# Analog_Inputs.net
KiCad netlist of a schematic drawn in Altium Designer
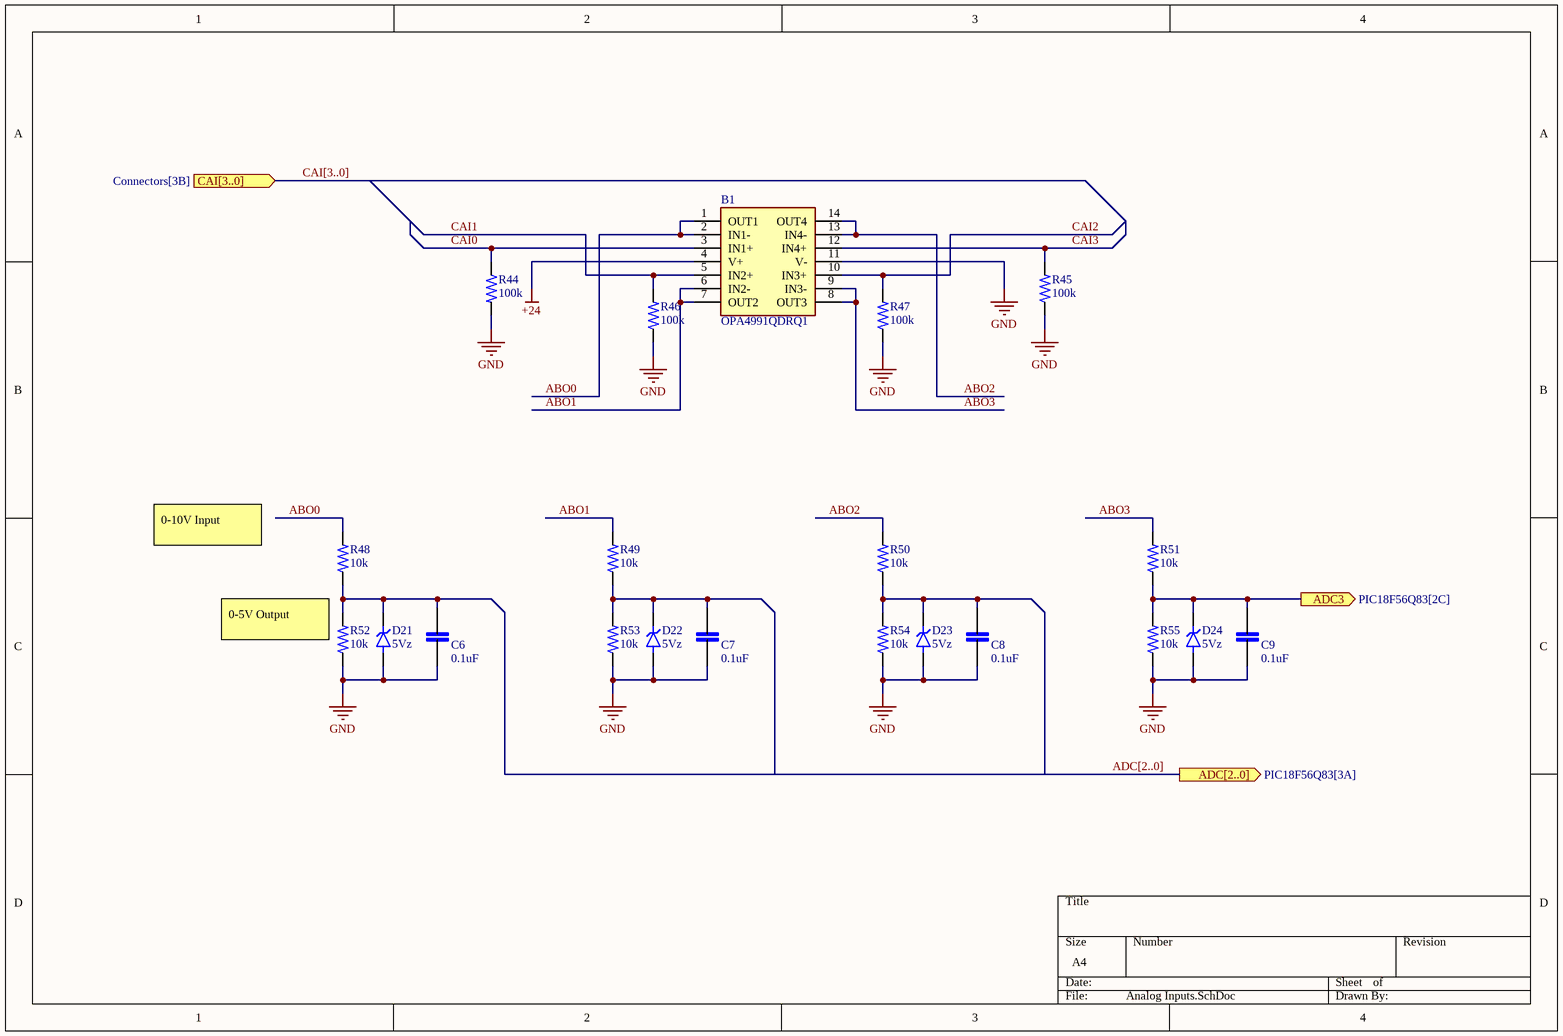
[diagram p0: Analog Inputs.SchDoc]

(export (version "E")
  (design (tool "Eeschema 10.0.6"))
  (components
    (comp (ref "B1")
      (value "OPA4991QDRQ1")
      (footprint "OPA4991QDRQ1")
      (fields (field (name "MOUSER PART NUMBER") "595-OPA4991QDRQ1"))
      (libsource (lib "OP AMP") (part "OPA4991QDRQ1"))
    )
    (comp (ref "C6")
      (value "0.1uF")
      (footprint "0805")
      (fields (field (name "MP") "LD051A121KAB2A") (field (name "MF") "AVX"))
      (libsource (lib "Capacitors SMD") (part "0805_Capacitor"))
    )
    (comp (ref "C7")
      (value "0.1uF")
      (footprint "0805")
      (fields (field (name "MP") "LD051A121KAB2A") (field (name "MF") "AVX"))
      (libsource (lib "Capacitors SMD") (part "0805_Capacitor"))
    )
    (comp (ref "C8")
      (value "0.1uF")
      (footprint "0805")
      (fields (field (name "MP") "LD051A121KAB2A") (field (name "MF") "AVX"))
      (libsource (lib "Capacitors SMD") (part "0805_Capacitor"))
    )
    (comp (ref "C9")
      (value "0.1uF")
      (footprint "0805")
      (fields (field (name "MP") "LD051A121KAB2A") (field (name "MF") "AVX"))
      (libsource (lib "Capacitors SMD") (part "0805_Capacitor"))
    )
    (comp (ref "D21")
      (value "5Vz")
      (footprint "SOD123")
      (fields (field (name "MP") "1SMA5926") (field (name "MF") "Taiwan Semiconductor"))
      (libsource (lib "Diodes SMD") (part "SOD123 - Zener Diode"))
    )
    (comp (ref "D22")
      (value "5Vz")
      (footprint "SOD123")
      (fields (field (name "MP") "1SMA5926") (field (name "MF") "Taiwan Semiconductor"))
      (libsource (lib "Diodes SMD") (part "SOD123 - Zener Diode"))
    )
    (comp (ref "D23")
      (value "5Vz")
      (footprint "SOD123")
      (fields (field (name "MP") "1SMA5926") (field (name "MF") "Taiwan Semiconductor"))
      (libsource (lib "Diodes SMD") (part "SOD123 - Zener Diode"))
    )
    (comp (ref "D24")
      (value "5Vz")
      (footprint "SOD123")
      (fields (field (name "MP") "1SMA5926") (field (name "MF") "Taiwan Semiconductor"))
      (libsource (lib "Diodes SMD") (part "SOD123 - Zener Diode"))
    )
    (comp (ref "R44")
      (value "100k")
      (footprint "0805")
      (fields
        (field (name "MP") "2-2176053-0")
        (field (name "TOLERANCE") "1%")
        (field (name "MF") "TE Connectivity")
      )
      (libsource (lib "Resistors SMD") (part "0805_Resistor"))
    )
    (comp (ref "R45")
      (value "100k")
      (footprint "0805")
      (fields
        (field (name "MP") "2-2176053-0")
        (field (name "TOLERANCE") "1%")
        (field (name "MF") "TE Connectivity")
      )
      (libsource (lib "Resistors SMD") (part "0805_Resistor"))
    )
    (comp (ref "R46")
      (value "100k")
      (footprint "0805")
      (fields
        (field (name "MP") "2-2176053-0")
        (field (name "TOLERANCE") "1%")
        (field (name "MF") "TE Connectivity")
      )
      (libsource (lib "Resistors SMD") (part "0805_Resistor"))
    )
    (comp (ref "R47")
      (value "100k")
      (footprint "0805")
      (fields
        (field (name "MP") "2-2176053-0")
        (field (name "TOLERANCE") "1%")
        (field (name "MF") "TE Connectivity")
      )
      (libsource (lib "Resistors SMD") (part "0805_Resistor"))
    )
    (comp (ref "R48")
      (value "10k")
      (footprint "0805")
      (fields
        (field (name "MP") "2-2176053-0")
        (field (name "TOLERANCE") "1%")
        (field (name "MF") "TE Connectivity")
      )
      (libsource (lib "Resistors SMD") (part "0805_Resistor"))
    )
    (comp (ref "R49")
      (value "10k")
      (footprint "0805")
      (fields
        (field (name "MP") "2-2176053-0")
        (field (name "TOLERANCE") "1%")
        (field (name "MF") "TE Connectivity")
      )
      (libsource (lib "Resistors SMD") (part "0805_Resistor"))
    )
    (comp (ref "R50")
      (value "10k")
      (footprint "0805")
      (fields
        (field (name "MP") "2-2176053-0")
        (field (name "TOLERANCE") "1%")
        (field (name "MF") "TE Connectivity")
      )
      (libsource (lib "Resistors SMD") (part "0805_Resistor"))
    )
    (comp (ref "R51")
      (value "10k")
      (footprint "0805")
      (fields
        (field (name "MP") "2-2176053-0")
        (field (name "TOLERANCE") "1%")
        (field (name "MF") "TE Connectivity")
      )
      (libsource (lib "Resistors SMD") (part "0805_Resistor"))
    )
    (comp (ref "R52")
      (value "10k")
      (footprint "0805")
      (fields
        (field (name "MP") "2-2176053-0")
        (field (name "TOLERANCE") "1%")
        (field (name "MF") "TE Connectivity")
      )
      (libsource (lib "Resistors SMD") (part "0805_Resistor"))
    )
    (comp (ref "R53")
      (value "10k")
      (footprint "0805")
      (fields
        (field (name "MP") "2-2176053-0")
        (field (name "TOLERANCE") "1%")
        (field (name "MF") "TE Connectivity")
      )
      (libsource (lib "Resistors SMD") (part "0805_Resistor"))
    )
    (comp (ref "R54")
      (value "10k")
      (footprint "0805")
      (fields
        (field (name "MP") "2-2176053-0")
        (field (name "TOLERANCE") "1%")
        (field (name "MF") "TE Connectivity")
      )
      (libsource (lib "Resistors SMD") (part "0805_Resistor"))
    )
    (comp (ref "R55")
      (value "10k")
      (footprint "0805")
      (fields
        (field (name "MP") "2-2176053-0")
        (field (name "TOLERANCE") "1%")
        (field (name "MF") "TE Connectivity")
      )
      (libsource (lib "Resistors SMD") (part "0805_Resistor"))
    )
  )
  (nets
    (net (code "4") (name "+24") (class "Default")
      (node (ref "B1") (pin "4") (pinfunction "V+_4") (pintype "passive"))
    )
    (net (code "5") (name "/ABO0") (class "Default")
      (node (ref "B1") (pin "1") (pinfunction "OUT1_1") (pintype "passive"))
      (node (ref "B1") (pin "2") (pinfunction "IN1-_2") (pintype "passive"))
      (node (ref "R48") (pin "2") (pinfunction "2_2") (pintype "passive"))
    )
    (net (code "6") (name "/ABO1") (class "Default")
      (node (ref "B1") (pin "6") (pinfunction "IN2-_6") (pintype "passive"))
      (node (ref "B1") (pin "7") (pinfunction "OUT2_7") (pintype "passive"))
      (node (ref "R49") (pin "2") (pinfunction "2_2") (pintype "passive"))
    )
    (net (code "7") (name "/ABO2") (class "Default")
      (node (ref "B1") (pin "13") (pinfunction "IN4-_13") (pintype "passive"))
      (node (ref "B1") (pin "14") (pinfunction "OUT4_14") (pintype "passive"))
      (node (ref "R50") (pin "2") (pinfunction "2_2") (pintype "passive"))
    )
    (net (code "8") (name "/ABO3") (class "Default")
      (node (ref "B1") (pin "8") (pinfunction "OUT3_8") (pintype "passive"))
      (node (ref "B1") (pin "9") (pinfunction "IN3-_9") (pintype "passive"))
      (node (ref "R51") (pin "2") (pinfunction "2_2") (pintype "passive"))
    )
    (net (code "9") (name "/ADC3") (class "Default")
      (node (ref "C9") (pin "2") (pinfunction "2_2") (pintype "passive"))
      (node (ref "D24") (pin "1") (pinfunction "K_1") (pintype "passive"))
      (node (ref "R51") (pin "1") (pinfunction "1_1") (pintype "passive"))
      (node (ref "R55") (pin "2") (pinfunction "2_2") (pintype "passive"))
    )
    (net (code "11") (name "/CAI0") (class "Default")
      (node (ref "B1") (pin "3") (pinfunction "IN1+_3") (pintype "passive"))
      (node (ref "R44") (pin "1") (pinfunction "1_1") (pintype "passive"))
    )
    (net (code "12") (name "/CAI1") (class "Default")
      (node (ref "B1") (pin "5") (pinfunction "IN2+_5") (pintype "passive"))
      (node (ref "R46") (pin "2") (pinfunction "2_2") (pintype "passive"))
    )
    (net (code "13") (name "/CAI2") (class "Default")
      (node (ref "B1") (pin "10") (pinfunction "IN3+_10") (pintype "passive"))
      (node (ref "R47") (pin "2") (pinfunction "2_2") (pintype "passive"))
    )
    (net (code "14") (name "/CAI3") (class "Default")
      (node (ref "B1") (pin "12") (pinfunction "IN4+_12") (pintype "passive"))
      (node (ref "R45") (pin "2") (pinfunction "2_2") (pintype "passive"))
    )
    (net (code "16") (name "GND") (class "Default")
      (node (ref "B1") (pin "11") (pinfunction "V-_11") (pintype "passive"))
      (node (ref "C6") (pin "1") (pinfunction "1_1") (pintype "passive"))
      (node (ref "C7") (pin "1") (pinfunction "1_1") (pintype "passive"))
      (node (ref "C8") (pin "1") (pinfunction "1_1") (pintype "passive"))
      (node (ref "C9") (pin "1") (pinfunction "1_1") (pintype "passive"))
      (node (ref "D21") (pin "2") (pinfunction "A_2") (pintype "passive"))
      (node (ref "D22") (pin "2") (pinfunction "A_2") (pintype "passive"))
      (node (ref "D23") (pin "2") (pinfunction "A_2") (pintype "passive"))
      (node (ref "D24") (pin "2") (pinfunction "A_2") (pintype "passive"))
      (node (ref "R44") (pin "2") (pinfunction "2_2") (pintype "passive"))
      (node (ref "R45") (pin "1") (pinfunction "1_1") (pintype "passive"))
      (node (ref "R46") (pin "1") (pinfunction "1_1") (pintype "passive"))
      (node (ref "R47") (pin "1") (pinfunction "1_1") (pintype "passive"))
      (node (ref "R52") (pin "1") (pinfunction "1_1") (pintype "passive"))
      (node (ref "R53") (pin "1") (pinfunction "1_1") (pintype "passive"))
      (node (ref "R54") (pin "1") (pinfunction "1_1") (pintype "passive"))
      (node (ref "R55") (pin "1") (pinfunction "1_1") (pintype "passive"))
    )
    (net (code "17") (name "Net-(D21-K)") (class "Default")
      (node (ref "C6") (pin "2") (pinfunction "2_2") (pintype "passive"))
      (node (ref "D21") (pin "1") (pinfunction "K_1") (pintype "passive"))
      (node (ref "R48") (pin "1") (pinfunction "1_1") (pintype "passive"))
      (node (ref "R52") (pin "2") (pinfunction "2_2") (pintype "passive"))
    )
    (net (code "18") (name "Net-(D22-K)") (class "Default")
      (node (ref "C7") (pin "2") (pinfunction "2_2") (pintype "passive"))
      (node (ref "D22") (pin "1") (pinfunction "K_1") (pintype "passive"))
      (node (ref "R49") (pin "1") (pinfunction "1_1") (pintype "passive"))
      (node (ref "R53") (pin "2") (pinfunction "2_2") (pintype "passive"))
    )
    (net (code "19") (name "Net-(D23-K)") (class "Default")
      (node (ref "C8") (pin "2") (pinfunction "2_2") (pintype "passive"))
      (node (ref "D23") (pin "1") (pinfunction "K_1") (pintype "passive"))
      (node (ref "R50") (pin "1") (pinfunction "1_1") (pintype "passive"))
      (node (ref "R54") (pin "2") (pinfunction "2_2") (pintype "passive"))
    )
  )
)
